# vcf_lp_4p_24db-rev2.net
KiCad netlist of a schematic drawn in EAGLE
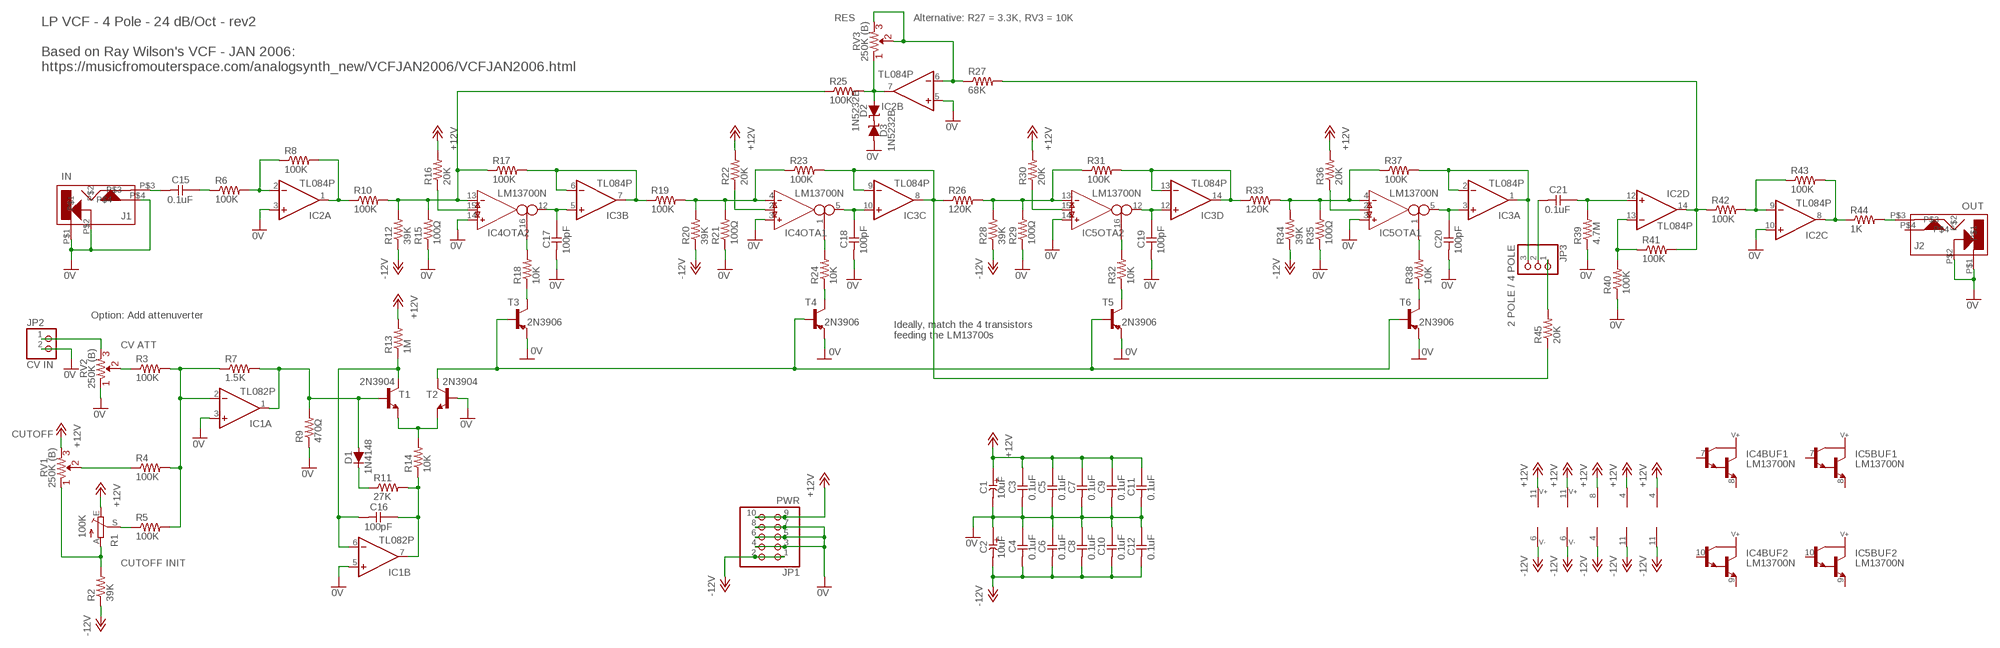
[diagram p0: schematic, sheet 1]

(export (version "E")
  (design (tool "Eeschema 10.0.6"))
  (components
    (comp (ref "C1")
      (value "10uF")
      (footprint "eagle-import:E2-5")
      (libsource (lib "eagle-import") (part "CE-USE2-5"))
    )
    (comp (ref "C2")
      (value "10uF")
      (footprint "eagle-import:E2-5")
      (libsource (lib "eagle-import") (part "CE-USE2-5"))
    )
    (comp (ref "C3")
      (value "0.1uF")
      (footprint "eagle-import:C025-024X044")
      (libsource (lib "eagle-import") (part "CC-US025-024X044"))
    )
    (comp (ref "C4")
      (value "0.1uF")
      (footprint "eagle-import:C025-024X044")
      (libsource (lib "eagle-import") (part "CC-US025-024X044"))
    )
    (comp (ref "C5")
      (value "0.1uF")
      (footprint "eagle-import:C025-024X044")
      (libsource (lib "eagle-import") (part "CC-US025-024X044"))
    )
    (comp (ref "C6")
      (value "0.1uF")
      (footprint "eagle-import:C025-024X044")
      (libsource (lib "eagle-import") (part "CC-US025-024X044"))
    )
    (comp (ref "C7")
      (value "0.1uF")
      (footprint "eagle-import:C025-024X044")
      (libsource (lib "eagle-import") (part "CC-US025-024X044"))
    )
    (comp (ref "C8")
      (value "0.1uF")
      (footprint "eagle-import:C025-024X044")
      (libsource (lib "eagle-import") (part "CC-US025-024X044"))
    )
    (comp (ref "C9")
      (value "0.1uF")
      (footprint "eagle-import:C025-024X044")
      (libsource (lib "eagle-import") (part "CC-US025-024X044"))
    )
    (comp (ref "C10")
      (value "0.1uF")
      (footprint "eagle-import:C025-024X044")
      (libsource (lib "eagle-import") (part "CC-US025-024X044"))
    )
    (comp (ref "C11")
      (value "0.1uF")
      (footprint "eagle-import:C025-024X044")
      (libsource (lib "eagle-import") (part "CC-US025-024X044"))
    )
    (comp (ref "C12")
      (value "0.1uF")
      (footprint "eagle-import:C025-024X044")
      (libsource (lib "eagle-import") (part "CC-US025-024X044"))
    )
    (comp (ref "C15")
      (value "0.1uF")
      (footprint "eagle-import:C025-024X044")
      (libsource (lib "eagle-import") (part "CC-US025-024X044"))
    )
    (comp (ref "C16")
      (value "100pF")
      (footprint "eagle-import:C025-024X044")
      (libsource (lib "eagle-import") (part "CC-US025-024X044"))
    )
    (comp (ref "C17")
      (value "100pF")
      (footprint "eagle-import:C025-024X044")
      (libsource (lib "eagle-import") (part "CC-US025-024X044"))
    )
    (comp (ref "C18")
      (value "100pF")
      (footprint "eagle-import:C025-024X044")
      (libsource (lib "eagle-import") (part "CC-US025-024X044"))
    )
    (comp (ref "C19")
      (value "100pF")
      (footprint "eagle-import:C025-024X044")
      (libsource (lib "eagle-import") (part "CC-US025-024X044"))
    )
    (comp (ref "C20")
      (value "100pF")
      (footprint "eagle-import:C025-024X044")
      (libsource (lib "eagle-import") (part "CC-US025-024X044"))
    )
    (comp (ref "C21")
      (value "0.1uF")
      (footprint "eagle-import:C025-024X044")
      (libsource (lib "eagle-import") (part "CC-US025-024X044"))
    )
    (comp (ref "D1")
      (value "1N4148")
      (footprint "eagle-import:DO35-7")
      (libsource (lib "eagle-import") (part "1N4148"))
    )
    (comp (ref "D2")
      (value "1N5232B")
      (footprint "eagle-import:DO34-5")
      (libsource (lib "eagle-import") (part "1N5232B"))
    )
    (comp (ref "D3")
      (value "1N5232B")
      (footprint "eagle-import:DO34-5")
      (libsource (lib "eagle-import") (part "1N5232B"))
    )
    (comp (ref "IC1")
      (value "TL082P")
      (footprint "eagle-import:DIL08")
      (libsource (lib "eagle-import") (part "TL082P"))
    )
    (comp (ref "IC2")
      (value "TL084P")
      (footprint "eagle-import:DIL14")
      (libsource (lib "eagle-import") (part "TL084P"))
    )
    (comp (ref "IC3")
      (value "TL084P")
      (footprint "eagle-import:DIL14")
      (libsource (lib "eagle-import") (part "TL084P"))
    )
    (comp (ref "IC4")
      (value "LM13700N")
      (footprint "eagle-import:DIL16")
      (libsource (lib "eagle-import") (part "LM13700N"))
    )
    (comp (ref "IC5")
      (value "LM13700N")
      (footprint "eagle-import:DIL16")
      (libsource (lib "eagle-import") (part "LM13700N"))
    )
    (comp (ref "J1")
      (value "IN")
      (footprint "eagle-import:CL1384")
      (libsource (lib "eagle-import") (part "CL1384"))
    )
    (comp (ref "J2")
      (value "OUT")
      (footprint "eagle-import:CL1384")
      (libsource (lib "eagle-import") (part "CL1384"))
    )
    (comp (ref "JP1")
      (value "PWR")
      (footprint "eagle-import:2X05")
      (libsource (lib "eagle-import") (part "PINHD-2X5"))
    )
    (comp (ref "JP2")
      (value "CV IN")
      (footprint "eagle-import:1X02")
      (libsource (lib "eagle-import") (part "PINHD-1X2"))
    )
    (comp (ref "JP3")
      (value "2 POLE / 4 POLE")
      (footprint "eagle-import:1X03")
      (libsource (lib "eagle-import") (part "PINHD-1X3"))
    )
    (comp (ref "R1")
      (value "100K")
      (footprint "eagle-import:CA6V")
      (libsource (lib "eagle-import") (part "TRIM_EU-CA6V"))
    )
    (comp (ref "R2")
      (value "39K")
      (footprint "eagle-import:0207_7")
      (libsource (lib "eagle-import") (part "R-US_0207/7"))
    )
    (comp (ref "R3")
      (value "100K")
      (footprint "eagle-import:0207_7")
      (libsource (lib "eagle-import") (part "R-US_0207/7"))
    )
    (comp (ref "R4")
      (value "100K")
      (footprint "eagle-import:0207_7")
      (libsource (lib "eagle-import") (part "R-US_0207/7"))
    )
    (comp (ref "R5")
      (value "100K")
      (footprint "eagle-import:0207_7")
      (libsource (lib "eagle-import") (part "R-US_0207/7"))
    )
    (comp (ref "R6")
      (value "100K")
      (footprint "eagle-import:0207_7")
      (libsource (lib "eagle-import") (part "R-US_0207/7"))
    )
    (comp (ref "R7")
      (value "1.5K")
      (footprint "eagle-import:0207_7")
      (libsource (lib "eagle-import") (part "R-US_0207/7"))
    )
    (comp (ref "R8")
      (value "100K")
      (footprint "eagle-import:0207_7")
      (libsource (lib "eagle-import") (part "R-US_0207/7"))
    )
    (comp (ref "R9")
      (value "470Ω")
      (footprint "eagle-import:0207_7")
      (libsource (lib "eagle-import") (part "R-US_0207/7"))
    )
    (comp (ref "R10")
      (value "100K")
      (footprint "eagle-import:0207_7")
      (libsource (lib "eagle-import") (part "R-US_0207/7"))
    )
    (comp (ref "R11")
      (value "27K")
      (footprint "eagle-import:0207_7")
      (libsource (lib "eagle-import") (part "R-US_0207/7"))
    )
    (comp (ref "R12")
      (value "39K")
      (footprint "eagle-import:0207_7")
      (libsource (lib "eagle-import") (part "R-US_0207/7"))
    )
    (comp (ref "R13")
      (value "1M")
      (footprint "eagle-import:0207_7")
      (libsource (lib "eagle-import") (part "R-US_0207/7"))
    )
    (comp (ref "R14")
      (value "10K")
      (footprint "eagle-import:0207_7")
      (libsource (lib "eagle-import") (part "R-US_0207/7"))
    )
    (comp (ref "R15")
      (value "100Ω")
      (footprint "eagle-import:0207_7")
      (libsource (lib "eagle-import") (part "R-US_0207/7"))
    )
    (comp (ref "R16")
      (value "20K")
      (footprint "eagle-import:0207_7")
      (libsource (lib "eagle-import") (part "R-US_0207/7"))
    )
    (comp (ref "R17")
      (value "100K")
      (footprint "eagle-import:0207_7")
      (libsource (lib "eagle-import") (part "R-US_0207/7"))
    )
    (comp (ref "R18")
      (value "10K")
      (footprint "eagle-import:0207_7")
      (libsource (lib "eagle-import") (part "R-US_0207/7"))
    )
    (comp (ref "R19")
      (value "100K")
      (footprint "eagle-import:0207_7")
      (libsource (lib "eagle-import") (part "R-US_0207/7"))
    )
    (comp (ref "R20")
      (value "39K")
      (footprint "eagle-import:0207_7")
      (libsource (lib "eagle-import") (part "R-US_0207/7"))
    )
    (comp (ref "R21")
      (value "100Ω")
      (footprint "eagle-import:0207_7")
      (libsource (lib "eagle-import") (part "R-US_0207/7"))
    )
    (comp (ref "R22")
      (value "20K")
      (footprint "eagle-import:0207_7")
      (libsource (lib "eagle-import") (part "R-US_0207/7"))
    )
    (comp (ref "R23")
      (value "100K")
      (footprint "eagle-import:0207_7")
      (libsource (lib "eagle-import") (part "R-US_0207/7"))
    )
    (comp (ref "R24")
      (value "10K")
      (footprint "eagle-import:0207_7")
      (libsource (lib "eagle-import") (part "R-US_0207/7"))
    )
    (comp (ref "R25")
      (value "100K")
      (footprint "eagle-import:0207_7")
      (libsource (lib "eagle-import") (part "R-US_0207/7"))
    )
    (comp (ref "R26")
      (value "120K")
      (footprint "eagle-import:0207_7")
      (libsource (lib "eagle-import") (part "R-US_0207/7"))
    )
    (comp (ref "R27")
      (value "68K")
      (footprint "eagle-import:0207_7")
      (libsource (lib "eagle-import") (part "R-US_0207/7"))
    )
    (comp (ref "R28")
      (value "39K")
      (footprint "eagle-import:0207_7")
      (libsource (lib "eagle-import") (part "R-US_0207/7"))
    )
    (comp (ref "R29")
      (value "100Ω")
      (footprint "eagle-import:0207_7")
      (libsource (lib "eagle-import") (part "R-US_0207/7"))
    )
    (comp (ref "R30")
      (value "20K")
      (footprint "eagle-import:0207_7")
      (libsource (lib "eagle-import") (part "R-US_0207/7"))
    )
    (comp (ref "R31")
      (value "100K")
      (footprint "eagle-import:0207_7")
      (libsource (lib "eagle-import") (part "R-US_0207/7"))
    )
    (comp (ref "R32")
      (value "10K")
      (footprint "eagle-import:0207_7")
      (libsource (lib "eagle-import") (part "R-US_0207/7"))
    )
    (comp (ref "R33")
      (value "120K")
      (footprint "eagle-import:0207_7")
      (libsource (lib "eagle-import") (part "R-US_0207/7"))
    )
    (comp (ref "R34")
      (value "39K")
      (footprint "eagle-import:0207_7")
      (libsource (lib "eagle-import") (part "R-US_0207/7"))
    )
    (comp (ref "R35")
      (value "100Ω")
      (footprint "eagle-import:0207_7")
      (libsource (lib "eagle-import") (part "R-US_0207/7"))
    )
    (comp (ref "R36")
      (value "20K")
      (footprint "eagle-import:0207_7")
      (libsource (lib "eagle-import") (part "R-US_0207/7"))
    )
    (comp (ref "R37")
      (value "100K")
      (footprint "eagle-import:0207_7")
      (libsource (lib "eagle-import") (part "R-US_0207/7"))
    )
    (comp (ref "R38")
      (value "10K")
      (footprint "eagle-import:0207_7")
      (libsource (lib "eagle-import") (part "R-US_0207/7"))
    )
    (comp (ref "R39")
      (value "4.7M")
      (footprint "eagle-import:0207_7")
      (libsource (lib "eagle-import") (part "R-US_0207/7"))
    )
    (comp (ref "R40")
      (value "100K")
      (footprint "eagle-import:0207_7")
      (libsource (lib "eagle-import") (part "R-US_0207/7"))
    )
    (comp (ref "R41")
      (value "100K")
      (footprint "eagle-import:0207_7")
      (libsource (lib "eagle-import") (part "R-US_0207/7"))
    )
    (comp (ref "R42")
      (value "100K")
      (footprint "eagle-import:0207_7")
      (libsource (lib "eagle-import") (part "R-US_0207/7"))
    )
    (comp (ref "R43")
      (value "100K")
      (footprint "eagle-import:0207_7")
      (libsource (lib "eagle-import") (part "R-US_0207/7"))
    )
    (comp (ref "R44")
      (value "1K")
      (footprint "eagle-import:0207_7")
      (libsource (lib "eagle-import") (part "R-US_0207/7"))
    )
    (comp (ref "R45")
      (value "20K")
      (footprint "eagle-import:0207_7")
      (libsource (lib "eagle-import") (part "R-US_0207/7"))
    )
    (comp (ref "RV1")
      (value "250K (B)")
      (footprint "eagle-import:_COMMON_3RP_1610N")
      (libsource (lib "eagle-import") (part "R-VARR-VAR-10"))
    )
    (comp (ref "RV2")
      (value "250K (B)")
      (footprint "eagle-import:_COMMON_3RP_1610N")
      (libsource (lib "eagle-import") (part "R-VARR-VAR-10"))
    )
    (comp (ref "RV3")
      (value "250K (B)")
      (footprint "eagle-import:_COMMON_3RP_1610N")
      (libsource (lib "eagle-import") (part "R-VARR-VAR-10"))
    )
    (comp (ref "T1")
      (value "2N3904")
      (footprint "eagle-import:TO92-EBC")
      (libsource (lib "eagle-import") (part "-NPN-TO92-EBC2N3904"))
    )
    (comp (ref "T2")
      (value "2N3904")
      (footprint "eagle-import:TO92-EBC")
      (libsource (lib "eagle-import") (part "-NPN-TO92-EBC2N3904"))
    )
    (comp (ref "T3")
      (value "2N3906")
      (footprint "eagle-import:TO92-EBC")
      (libsource (lib "eagle-import") (part "-PNP-TO92-EBC2N3906"))
    )
    (comp (ref "T4")
      (value "2N3906")
      (footprint "eagle-import:TO92-EBC")
      (libsource (lib "eagle-import") (part "-PNP-TO92-EBC2N3906"))
    )
    (comp (ref "T5")
      (value "2N3906")
      (footprint "eagle-import:TO92-EBC")
      (libsource (lib "eagle-import") (part "-PNP-TO92-EBC2N3906"))
    )
    (comp (ref "T6")
      (value "2N3906")
      (footprint "eagle-import:TO92-EBC")
      (libsource (lib "eagle-import") (part "-PNP-TO92-EBC2N3906"))
    )
  )
  (nets
    (net (code "1") (name "+12V") (class "Default")
      (node (ref "C1") (pin "+") (pinfunction "+_+") (pintype "passive"))
      (node (ref "C11") (pin "1") (pinfunction "1_1") (pintype "passive"))
      (node (ref "C3") (pin "1") (pinfunction "1_1") (pintype "passive"))
      (node (ref "C5") (pin "1") (pinfunction "1_1") (pintype "passive"))
      (node (ref "C7") (pin "1") (pinfunction "1_1") (pintype "passive"))
      (node (ref "C9") (pin "1") (pinfunction "1_1") (pintype "passive"))
      (node (ref "IC1") (pin "8") (pinfunction "V+_8") (pintype "power_in"))
      (node (ref "IC2") (pin "4") (pinfunction "V+_4") (pintype "power_in"))
      (node (ref "IC3") (pin "4") (pinfunction "V+_4") (pintype "power_in"))
      (node (ref "IC4") (pin "11") (pinfunction "V+_11") (pintype "power_in"))
      (node (ref "IC5") (pin "11") (pinfunction "V+_11") (pintype "power_in"))
      (node (ref "JP1") (pin "10") (pinfunction "10_10") (pintype "passive"))
      (node (ref "JP1") (pin "9") (pinfunction "9_9") (pintype "passive"))
      (node (ref "R1") (pin "E") (pinfunction "E_E") (pintype "passive"))
      (node (ref "R13") (pin "2") (pinfunction "2_2") (pintype "passive"))
      (node (ref "R16") (pin "2") (pinfunction "2_2") (pintype "passive"))
      (node (ref "R22") (pin "2") (pinfunction "2_2") (pintype "passive"))
      (node (ref "R30") (pin "2") (pinfunction "2_2") (pintype "passive"))
      (node (ref "R36") (pin "2") (pinfunction "2_2") (pintype "passive"))
      (node (ref "RV1") (pin "3") (pinfunction "3_3") (pintype "passive"))
    )
    (net (code "2") (name "-12V") (class "Default")
      (node (ref "C10") (pin "2") (pinfunction "2_2") (pintype "passive"))
      (node (ref "C12") (pin "2") (pinfunction "2_2") (pintype "passive"))
      (node (ref "C2") (pin "-") (pinfunction "-_-") (pintype "passive"))
      (node (ref "C4") (pin "2") (pinfunction "2_2") (pintype "passive"))
      (node (ref "C6") (pin "2") (pinfunction "2_2") (pintype "passive"))
      (node (ref "C8") (pin "2") (pinfunction "2_2") (pintype "passive"))
      (node (ref "IC1") (pin "4") (pinfunction "V-_4") (pintype "power_in"))
      (node (ref "IC2") (pin "11") (pinfunction "V-_11") (pintype "power_in"))
      (node (ref "IC3") (pin "11") (pinfunction "V-_11") (pintype "power_in"))
      (node (ref "IC4") (pin "6") (pinfunction "V-_6") (pintype "power_in"))
      (node (ref "IC5") (pin "6") (pinfunction "V-_6") (pintype "power_in"))
      (node (ref "JP1") (pin "1") (pinfunction "1_1") (pintype "passive"))
      (node (ref "JP1") (pin "2") (pinfunction "2_2") (pintype "passive"))
      (node (ref "R12") (pin "1") (pinfunction "1_1") (pintype "passive"))
      (node (ref "R2") (pin "1") (pinfunction "1_1") (pintype "passive"))
      (node (ref "R20") (pin "1") (pinfunction "1_1") (pintype "passive"))
      (node (ref "R28") (pin "1") (pinfunction "1_1") (pintype "passive"))
      (node (ref "R34") (pin "1") (pinfunction "1_1") (pintype "passive"))
    )
    (net (code "3") (name "0V") (class "Default")
      (node (ref "C1") (pin "-") (pinfunction "-_-") (pintype "passive"))
      (node (ref "C10") (pin "1") (pinfunction "1_1") (pintype "passive"))
      (node (ref "C11") (pin "2") (pinfunction "2_2") (pintype "passive"))
      (node (ref "C12") (pin "1") (pinfunction "1_1") (pintype "passive"))
      (node (ref "C17") (pin "2") (pinfunction "2_2") (pintype "passive"))
      (node (ref "C18") (pin "2") (pinfunction "2_2") (pintype "passive"))
      (node (ref "C19") (pin "2") (pinfunction "2_2") (pintype "passive"))
      (node (ref "C2") (pin "+") (pinfunction "+_+") (pintype "passive"))
      (node (ref "C20") (pin "2") (pinfunction "2_2") (pintype "passive"))
      (node (ref "C3") (pin "2") (pinfunction "2_2") (pintype "passive"))
      (node (ref "C4") (pin "1") (pinfunction "1_1") (pintype "passive"))
      (node (ref "C5") (pin "2") (pinfunction "2_2") (pintype "passive"))
      (node (ref "C6") (pin "1") (pinfunction "1_1") (pintype "passive"))
      (node (ref "C7") (pin "2") (pinfunction "2_2") (pintype "passive"))
      (node (ref "C8") (pin "1") (pinfunction "1_1") (pintype "passive"))
      (node (ref "C9") (pin "2") (pinfunction "2_2") (pintype "passive"))
      (node (ref "D3") (pin "A") (pinfunction "A_A") (pintype "passive"))
      (node (ref "IC1") (pin "3") (pinfunction "+IN_3") (pintype "input"))
      (node (ref "IC1") (pin "5") (pinfunction "+IN_5") (pintype "input"))
      (node (ref "IC2") (pin "10") (pinfunction "+IN_10") (pintype "input"))
      (node (ref "IC2") (pin "3") (pinfunction "+IN_3") (pintype "input"))
      (node (ref "IC2") (pin "5") (pinfunction "+IN_5") (pintype "input"))
      (node (ref "IC4") (pin "14") (pinfunction "IN_P_14") (pintype "input"))
      (node (ref "IC4") (pin "3") (pinfunction "IN_P_3") (pintype "input"))
      (node (ref "IC5") (pin "14") (pinfunction "IN_P_14") (pintype "input"))
      (node (ref "IC5") (pin "3") (pinfunction "IN_P_3") (pintype "input"))
      (node (ref "J1") (pin "P$1") (pinfunction "P$1_P$1") (pintype "bidirectional"))
      (node (ref "J1") (pin "P$2") (pinfunction "P$2_P$2") (pintype "bidirectional"))
      (node (ref "J1") (pin "P$4") (pinfunction "P$4_P$4") (pintype "bidirectional"))
      (node (ref "J2") (pin "P$1") (pinfunction "P$1_P$1") (pintype "bidirectional"))
      (node (ref "J2") (pin "P$2") (pinfunction "P$2_P$2") (pintype "bidirectional"))
      (node (ref "JP1") (pin "3") (pinfunction "3_3") (pintype "passive"))
      (node (ref "JP1") (pin "4") (pinfunction "4_4") (pintype "passive"))
      (node (ref "JP1") (pin "5") (pinfunction "5_5") (pintype "passive"))
      (node (ref "JP1") (pin "6") (pinfunction "6_6") (pintype "passive"))
      (node (ref "JP1") (pin "7") (pinfunction "7_7") (pintype "passive"))
      (node (ref "JP1") (pin "8") (pinfunction "8_8") (pintype "passive"))
      (node (ref "JP2") (pin "2") (pinfunction "2_2") (pintype "passive"))
      (node (ref "R15") (pin "1") (pinfunction "1_1") (pintype "passive"))
      (node (ref "R21") (pin "1") (pinfunction "1_1") (pintype "passive"))
      (node (ref "R29") (pin "1") (pinfunction "1_1") (pintype "passive"))
      (node (ref "R35") (pin "1") (pinfunction "1_1") (pintype "passive"))
      (node (ref "R39") (pin "1") (pinfunction "1_1") (pintype "passive"))
      (node (ref "R40") (pin "1") (pinfunction "1_1") (pintype "passive"))
      (node (ref "R9") (pin "1") (pinfunction "1_1") (pintype "passive"))
      (node (ref "RV2") (pin "1") (pinfunction "1_1") (pintype "passive"))
      (node (ref "T2") (pin "B") (pinfunction "B_B") (pintype "passive"))
      (node (ref "T3") (pin "E") (pinfunction "E_E") (pintype "passive"))
      (node (ref "T4") (pin "E") (pinfunction "E_E") (pintype "passive"))
      (node (ref "T5") (pin "E") (pinfunction "E_E") (pintype "passive"))
      (node (ref "T6") (pin "E") (pinfunction "E_E") (pintype "passive"))
    )
    (net (code "4") (name "Net-(C15-Pad1)") (class "Default")
      (node (ref "C15") (pin "1") (pinfunction "1_1") (pintype "passive"))
      (node (ref "R6") (pin "1") (pinfunction "1_1") (pintype "passive"))
    )
    (net (code "5") (name "Net-(C15-Pad2)") (class "Default")
      (node (ref "C15") (pin "2") (pinfunction "2_2") (pintype "passive"))
      (node (ref "J1") (pin "P$3") (pinfunction "P$3_P$3") (pintype "bidirectional"))
    )
    (net (code "6") (name "Net-(C21-Pad2)") (class "Default")
      (node (ref "C21") (pin "2") (pinfunction "2_2") (pintype "passive"))
      (node (ref "JP3") (pin "2") (pinfunction "2_2") (pintype "passive"))
    )
    (net (code "7") (name "Net-(D1-PadC)") (class "Default")
      (node (ref "D1") (pin "C") (pinfunction "C_C") (pintype "passive"))
      (node (ref "R11") (pin "1") (pinfunction "1_1") (pintype "passive"))
    )
    (net (code "8") (name "Net-(D2-PadC)") (class "Default")
      (node (ref "D2") (pin "C") (pinfunction "C_C") (pintype "passive"))
      (node (ref "D3") (pin "C") (pinfunction "C_C") (pintype "passive"))
    )
    (net (code "9") (name "Net-(IC1A--IN)") (class "Default")
      (node (ref "IC1") (pin "2") (pinfunction "-IN_2") (pintype "input"))
      (node (ref "R3") (pin "2") (pinfunction "2_2") (pintype "passive"))
      (node (ref "R4") (pin "2") (pinfunction "2_2") (pintype "passive"))
      (node (ref "R5") (pin "2") (pinfunction "2_2") (pintype "passive"))
      (node (ref "R7") (pin "1") (pinfunction "1_1") (pintype "passive"))
    )
    (net (code "10") (name "Net-(IC1A-OUT)") (class "Default")
      (node (ref "D1") (pin "A") (pinfunction "A_A") (pintype "passive"))
      (node (ref "IC1") (pin "1") (pinfunction "OUT_1") (pintype "output"))
      (node (ref "R7") (pin "2") (pinfunction "2_2") (pintype "passive"))
      (node (ref "R9") (pin "2") (pinfunction "2_2") (pintype "passive"))
      (node (ref "T1") (pin "B") (pinfunction "B_B") (pintype "passive"))
    )
    (net (code "11") (name "Net-(IC1B--IN)") (class "Default")
      (node (ref "C16") (pin "2") (pinfunction "2_2") (pintype "passive"))
      (node (ref "IC1") (pin "6") (pinfunction "-IN_6") (pintype "input"))
      (node (ref "R13") (pin "1") (pinfunction "1_1") (pintype "passive"))
      (node (ref "T1") (pin "C") (pinfunction "C_C") (pintype "passive"))
    )
    (net (code "12") (name "Net-(IC1B-OUT)") (class "Default")
      (node (ref "C16") (pin "1") (pinfunction "1_1") (pintype "passive"))
      (node (ref "IC1") (pin "7") (pinfunction "OUT_7") (pintype "output"))
      (node (ref "R11") (pin "2") (pinfunction "2_2") (pintype "passive"))
      (node (ref "R14") (pin "1") (pinfunction "1_1") (pintype "passive"))
    )
    (net (code "13") (name "Net-(IC2A--IN)") (class "Default")
      (node (ref "IC2") (pin "2") (pinfunction "-IN_2") (pintype "input"))
      (node (ref "R6") (pin "2") (pinfunction "2_2") (pintype "passive"))
      (node (ref "R8") (pin "1") (pinfunction "1_1") (pintype "passive"))
    )
    (net (code "14") (name "Net-(IC2A-OUT)") (class "Default")
      (node (ref "IC2") (pin "1") (pinfunction "OUT_1") (pintype "output"))
      (node (ref "R10") (pin "1") (pinfunction "1_1") (pintype "passive"))
      (node (ref "R8") (pin "2") (pinfunction "2_2") (pintype "passive"))
    )
    (net (code "15") (name "Net-(IC2B--IN)") (class "Default")
      (node (ref "IC2") (pin "6") (pinfunction "-IN_6") (pintype "input"))
      (node (ref "R27") (pin "1") (pinfunction "1_1") (pintype "passive"))
      (node (ref "RV3") (pin "2") (pinfunction "2_2") (pintype "passive"))
      (node (ref "RV3") (pin "3") (pinfunction "3_3") (pintype "passive"))
    )
    (net (code "16") (name "Net-(IC2B-OUT)") (class "Default")
      (node (ref "D2") (pin "A") (pinfunction "A_A") (pintype "passive"))
      (node (ref "IC2") (pin "7") (pinfunction "OUT_7") (pintype "output"))
      (node (ref "R25") (pin "2") (pinfunction "2_2") (pintype "passive"))
      (node (ref "RV3") (pin "1") (pinfunction "1_1") (pintype "passive"))
    )
    (net (code "17") (name "Net-(IC2C--IN)") (class "Default")
      (node (ref "IC2") (pin "9") (pinfunction "-IN_9") (pintype "input"))
      (node (ref "R42") (pin "2") (pinfunction "2_2") (pintype "passive"))
      (node (ref "R43") (pin "1") (pinfunction "1_1") (pintype "passive"))
    )
    (net (code "18") (name "Net-(IC2C-OUT)") (class "Default")
      (node (ref "IC2") (pin "8") (pinfunction "OUT_8") (pintype "output"))
      (node (ref "R43") (pin "2") (pinfunction "2_2") (pintype "passive"))
      (node (ref "R44") (pin "1") (pinfunction "1_1") (pintype "passive"))
    )
    (net (code "19") (name "Net-(IC2D-+IN)") (class "Default")
      (node (ref "C21") (pin "1") (pinfunction "1_1") (pintype "passive"))
      (node (ref "IC2") (pin "12") (pinfunction "+IN_12") (pintype "input"))
      (node (ref "R39") (pin "2") (pinfunction "2_2") (pintype "passive"))
    )
    (net (code "20") (name "Net-(IC2D--IN)") (class "Default")
      (node (ref "IC2") (pin "13") (pinfunction "-IN_13") (pintype "input"))
      (node (ref "R40") (pin "2") (pinfunction "2_2") (pintype "passive"))
      (node (ref "R41") (pin "1") (pinfunction "1_1") (pintype "passive"))
    )
    (net (code "21") (name "Net-(IC2D-OUT)") (class "Default")
      (node (ref "IC2") (pin "14") (pinfunction "OUT_14") (pintype "output"))
      (node (ref "R27") (pin "2") (pinfunction "2_2") (pintype "passive"))
      (node (ref "R41") (pin "2") (pinfunction "2_2") (pintype "passive"))
      (node (ref "R42") (pin "1") (pinfunction "1_1") (pintype "passive"))
    )
    (net (code "22") (name "Net-(IC3A-+IN)") (class "Default")
      (node (ref "C20") (pin "1") (pinfunction "1_1") (pintype "passive"))
      (node (ref "IC3") (pin "3") (pinfunction "+IN_3") (pintype "input"))
      (node (ref "IC5") (pin "5") (pinfunction "OUT_5") (pintype "output"))
    )
    (net (code "23") (name "Net-(IC3A--IN)") (class "Default")
      (node (ref "IC3") (pin "1") (pinfunction "OUT_1") (pintype "output"))
      (node (ref "IC3") (pin "2") (pinfunction "-IN_2") (pintype "input"))
      (node (ref "JP3") (pin "3") (pinfunction "3_3") (pintype "passive"))
      (node (ref "R37") (pin "2") (pinfunction "2_2") (pintype "passive"))
    )
    (net (code "24") (name "Net-(IC3B-+IN)") (class "Default")
      (node (ref "C17") (pin "1") (pinfunction "1_1") (pintype "passive"))
      (node (ref "IC3") (pin "5") (pinfunction "+IN_5") (pintype "input"))
      (node (ref "IC4") (pin "12") (pinfunction "OUT_12") (pintype "output"))
    )
    (net (code "25") (name "Net-(IC3B--IN)") (class "Default")
      (node (ref "IC3") (pin "6") (pinfunction "-IN_6") (pintype "input"))
      (node (ref "IC3") (pin "7") (pinfunction "OUT_7") (pintype "output"))
      (node (ref "R17") (pin "2") (pinfunction "2_2") (pintype "passive"))
      (node (ref "R19") (pin "1") (pinfunction "1_1") (pintype "passive"))
    )
    (net (code "26") (name "Net-(IC3C-+IN)") (class "Default")
      (node (ref "C18") (pin "1") (pinfunction "1_1") (pintype "passive"))
      (node (ref "IC3") (pin "10") (pinfunction "+IN_10") (pintype "input"))
      (node (ref "IC4") (pin "5") (pinfunction "OUT_5") (pintype "output"))
    )
    (net (code "27") (name "Net-(IC3C--IN)") (class "Default")
      (node (ref "IC3") (pin "8") (pinfunction "OUT_8") (pintype "output"))
      (node (ref "IC3") (pin "9") (pinfunction "-IN_9") (pintype "input"))
      (node (ref "R23") (pin "2") (pinfunction "2_2") (pintype "passive"))
      (node (ref "R26") (pin "1") (pinfunction "1_1") (pintype "passive"))
      (node (ref "R45") (pin "1") (pinfunction "1_1") (pintype "passive"))
    )
    (net (code "28") (name "Net-(IC3D-+IN)") (class "Default")
      (node (ref "C19") (pin "1") (pinfunction "1_1") (pintype "passive"))
      (node (ref "IC3") (pin "12") (pinfunction "+IN_12") (pintype "input"))
      (node (ref "IC5") (pin "12") (pinfunction "OUT_12") (pintype "output"))
    )
    (net (code "29") (name "Net-(IC3D--IN)") (class "Default")
      (node (ref "IC3") (pin "13") (pinfunction "-IN_13") (pintype "input"))
      (node (ref "IC3") (pin "14") (pinfunction "OUT_14") (pintype "output"))
      (node (ref "R31") (pin "2") (pinfunction "2_2") (pintype "passive"))
      (node (ref "R33") (pin "1") (pinfunction "1_1") (pintype "passive"))
    )
    (net (code "30") (name "Net-(IC4C-IN_N)") (class "Default")
      (node (ref "IC4") (pin "4") (pinfunction "IN_N_4") (pintype "input"))
      (node (ref "R19") (pin "2") (pinfunction "2_2") (pintype "passive"))
      (node (ref "R20") (pin "2") (pinfunction "2_2") (pintype "passive"))
      (node (ref "R21") (pin "2") (pinfunction "2_2") (pintype "passive"))
      (node (ref "R23") (pin "1") (pinfunction "1_1") (pintype "passive"))
    )
    (net (code "31") (name "Net-(IC4C-I_BIAS)") (class "Default")
      (node (ref "IC4") (pin "1") (pinfunction "I_BIAS_1") (pintype "input"))
      (node (ref "R24") (pin "2") (pinfunction "2_2") (pintype "passive"))
    )
    (net (code "32") (name "Net-(IC4C-I_DIODE)") (class "Default")
      (node (ref "IC4") (pin "2") (pinfunction "I_DIODE_2") (pintype "input"))
      (node (ref "R22") (pin "1") (pinfunction "1_1") (pintype "passive"))
    )
    (net (code "33") (name "Net-(IC4D-IN_N)") (class "Default")
      (node (ref "IC4") (pin "13") (pinfunction "IN_N_13") (pintype "input"))
      (node (ref "R10") (pin "2") (pinfunction "2_2") (pintype "passive"))
      (node (ref "R12") (pin "2") (pinfunction "2_2") (pintype "passive"))
      (node (ref "R15") (pin "2") (pinfunction "2_2") (pintype "passive"))
      (node (ref "R17") (pin "1") (pinfunction "1_1") (pintype "passive"))
      (node (ref "R25") (pin "1") (pinfunction "1_1") (pintype "passive"))
    )
    (net (code "34") (name "Net-(IC4D-I_BIAS)") (class "Default")
      (node (ref "IC4") (pin "16") (pinfunction "I_BIAS_16") (pintype "input"))
      (node (ref "R18") (pin "2") (pinfunction "2_2") (pintype "passive"))
    )
    (net (code "35") (name "Net-(IC4D-I_DIODE)") (class "Default")
      (node (ref "IC4") (pin "15") (pinfunction "I_DIODE_15") (pintype "input"))
      (node (ref "R16") (pin "1") (pinfunction "1_1") (pintype "passive"))
    )
    (net (code "36") (name "Net-(IC5C-IN_N)") (class "Default")
      (node (ref "IC5") (pin "4") (pinfunction "IN_N_4") (pintype "input"))
      (node (ref "R33") (pin "2") (pinfunction "2_2") (pintype "passive"))
      (node (ref "R34") (pin "2") (pinfunction "2_2") (pintype "passive"))
      (node (ref "R35") (pin "2") (pinfunction "2_2") (pintype "passive"))
      (node (ref "R37") (pin "1") (pinfunction "1_1") (pintype "passive"))
    )
    (net (code "37") (name "Net-(IC5C-I_BIAS)") (class "Default")
      (node (ref "IC5") (pin "1") (pinfunction "I_BIAS_1") (pintype "input"))
      (node (ref "R38") (pin "2") (pinfunction "2_2") (pintype "passive"))
    )
    (net (code "38") (name "Net-(IC5C-I_DIODE)") (class "Default")
      (node (ref "IC5") (pin "2") (pinfunction "I_DIODE_2") (pintype "input"))
      (node (ref "R36") (pin "1") (pinfunction "1_1") (pintype "passive"))
    )
    (net (code "39") (name "Net-(IC5D-IN_N)") (class "Default")
      (node (ref "IC5") (pin "13") (pinfunction "IN_N_13") (pintype "input"))
      (node (ref "R26") (pin "2") (pinfunction "2_2") (pintype "passive"))
      (node (ref "R28") (pin "2") (pinfunction "2_2") (pintype "passive"))
      (node (ref "R29") (pin "2") (pinfunction "2_2") (pintype "passive"))
      (node (ref "R31") (pin "1") (pinfunction "1_1") (pintype "passive"))
    )
    (net (code "40") (name "Net-(IC5D-I_BIAS)") (class "Default")
      (node (ref "IC5") (pin "16") (pinfunction "I_BIAS_16") (pintype "input"))
      (node (ref "R32") (pin "2") (pinfunction "2_2") (pintype "passive"))
    )
    (net (code "41") (name "Net-(IC5D-I_DIODE)") (class "Default")
      (node (ref "IC5") (pin "15") (pinfunction "I_DIODE_15") (pintype "input"))
      (node (ref "R30") (pin "1") (pinfunction "1_1") (pintype "passive"))
    )
    (net (code "42") (name "Net-(J2-PadP$3)") (class "Default")
      (node (ref "J2") (pin "P$3") (pinfunction "P$3_P$3") (pintype "bidirectional"))
      (node (ref "R44") (pin "2") (pinfunction "2_2") (pintype "passive"))
    )
    (net (code "43") (name "Net-(JP2-Pad1)") (class "Default")
      (node (ref "JP2") (pin "1") (pinfunction "1_1") (pintype "passive"))
      (node (ref "RV2") (pin "3") (pinfunction "3_3") (pintype "passive"))
    )
    (net (code "44") (name "Net-(JP3-Pad1)") (class "Default")
      (node (ref "JP3") (pin "1") (pinfunction "1_1") (pintype "passive"))
      (node (ref "R45") (pin "2") (pinfunction "2_2") (pintype "passive"))
    )
    (net (code "45") (name "Net-(R1-PadA)") (class "Default")
      (node (ref "R1") (pin "A") (pinfunction "A_A") (pintype "passive"))
      (node (ref "R2") (pin "2") (pinfunction "2_2") (pintype "passive"))
      (node (ref "RV1") (pin "1") (pinfunction "1_1") (pintype "passive"))
    )
    (net (code "46") (name "Net-(R1-PadS)") (class "Default")
      (node (ref "R1") (pin "S") (pinfunction "S_S") (pintype "passive"))
      (node (ref "R5") (pin "1") (pinfunction "1_1") (pintype "passive"))
    )
    (net (code "47") (name "Net-(R3-Pad1)") (class "Default")
      (node (ref "R3") (pin "1") (pinfunction "1_1") (pintype "passive"))
      (node (ref "RV2") (pin "2") (pinfunction "2_2") (pintype "passive"))
    )
    (net (code "48") (name "Net-(R4-Pad1)") (class "Default")
      (node (ref "R4") (pin "1") (pinfunction "1_1") (pintype "passive"))
      (node (ref "RV1") (pin "2") (pinfunction "2_2") (pintype "passive"))
    )
    (net (code "49") (name "Net-(R14-Pad2)") (class "Default")
      (node (ref "R14") (pin "2") (pinfunction "2_2") (pintype "passive"))
      (node (ref "T1") (pin "E") (pinfunction "E_E") (pintype "passive"))
      (node (ref "T2") (pin "E") (pinfunction "E_E") (pintype "passive"))
    )
    (net (code "50") (name "Net-(R18-Pad1)") (class "Default")
      (node (ref "R18") (pin "1") (pinfunction "1_1") (pintype "passive"))
      (node (ref "T3") (pin "C") (pinfunction "C_C") (pintype "passive"))
    )
    (net (code "51") (name "Net-(R24-Pad1)") (class "Default")
      (node (ref "R24") (pin "1") (pinfunction "1_1") (pintype "passive"))
      (node (ref "T4") (pin "C") (pinfunction "C_C") (pintype "passive"))
    )
    (net (code "52") (name "Net-(R32-Pad1)") (class "Default")
      (node (ref "R32") (pin "1") (pinfunction "1_1") (pintype "passive"))
      (node (ref "T5") (pin "C") (pinfunction "C_C") (pintype "passive"))
    )
    (net (code "53") (name "Net-(R38-Pad1)") (class "Default")
      (node (ref "R38") (pin "1") (pinfunction "1_1") (pintype "passive"))
      (node (ref "T6") (pin "C") (pinfunction "C_C") (pintype "passive"))
    )
    (net (code "54") (name "Net-(T2-PadC)") (class "Default")
      (node (ref "T2") (pin "C") (pinfunction "C_C") (pintype "passive"))
      (node (ref "T3") (pin "B") (pinfunction "B_B") (pintype "passive"))
      (node (ref "T4") (pin "B") (pinfunction "B_B") (pintype "passive"))
      (node (ref "T5") (pin "B") (pinfunction "B_B") (pintype "passive"))
      (node (ref "T6") (pin "B") (pinfunction "B_B") (pintype "passive"))
    )
    (net (code "55") (name "unconnected-(IC4A-B-Pad7)") (class "Default")
      (node (ref "IC4") (pin "7") (pinfunction "B_7") (pintype "passive"))
    )
    (net (code "56") (name "unconnected-(IC4A-E-Pad8)") (class "Default")
      (node (ref "IC4") (pin "8") (pinfunction "E_8") (pintype "passive"))
    )
    (net (code "57") (name "unconnected-(IC4B-B-Pad10)") (class "Default")
      (node (ref "IC4") (pin "10") (pinfunction "B_10") (pintype "passive"))
    )
    (net (code "58") (name "unconnected-(IC4B-E-Pad9)") (class "Default")
      (node (ref "IC4") (pin "9") (pinfunction "E_9") (pintype "passive"))
    )
    (net (code "59") (name "unconnected-(IC5A-B-Pad7)") (class "Default")
      (node (ref "IC5") (pin "7") (pinfunction "B_7") (pintype "passive"))
    )
    (net (code "60") (name "unconnected-(IC5A-E-Pad8)") (class "Default")
      (node (ref "IC5") (pin "8") (pinfunction "E_8") (pintype "passive"))
    )
    (net (code "61") (name "unconnected-(IC5B-B-Pad10)") (class "Default")
      (node (ref "IC5") (pin "10") (pinfunction "B_10") (pintype "passive"))
    )
    (net (code "62") (name "unconnected-(IC5B-E-Pad9)") (class "Default")
      (node (ref "IC5") (pin "9") (pinfunction "E_9") (pintype "passive"))
    )
    (net (code "63") (name "unconnected-(J2-PadP$4)") (class "Default")
      (node (ref "J2") (pin "P$4") (pinfunction "P$4_P$4") (pintype "bidirectional"))
    )
  )
)
